# Cheat_Code.net
KiCad netlist of a schematic drawn in EAGLE
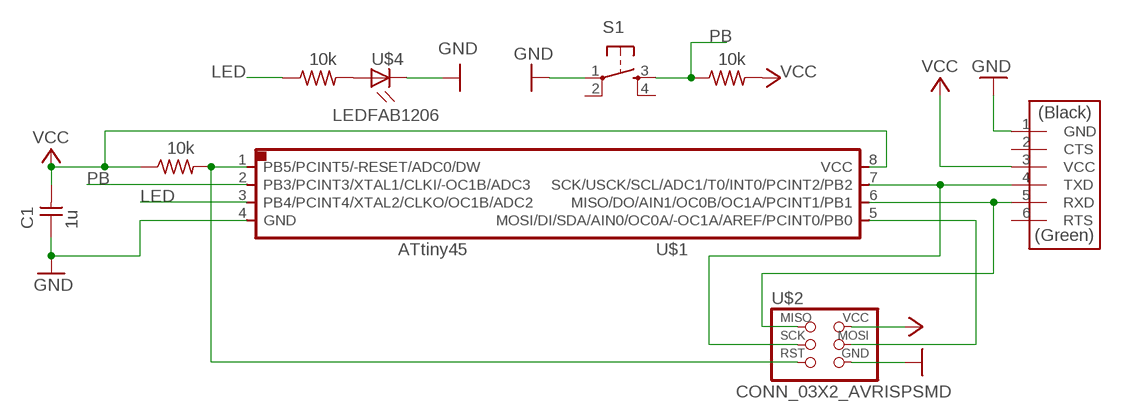
[diagram p0: schematic, sheet 1]

(export (version "E")
  (design (tool "Eeschema 10.0.6"))
  (components
    (comp (ref "C1")
      (value "1u")
      (footprint "eagle-import:C1206FAB")
      (libsource (lib "eagle-import") (part "CAP_UNPOLARIZEDFAB"))
    )
    (comp (ref "R1")
      (value "10k")
      (footprint "eagle-import:R1206")
      (libsource (lib "eagle-import") (part "R1206"))
    )
    (comp (ref "R2")
      (value "10k")
      (footprint "eagle-import:R1206")
      (libsource (lib "eagle-import") (part "R1206"))
    )
    (comp (ref "R3")
      (value "10k")
      (footprint "eagle-import:R1206")
      (libsource (lib "eagle-import") (part "R1206"))
    )
    (comp (ref "S1")
      (value "SW_SWITCH_TACTILE_6MM6MM_SWITCH")
      (footprint "eagle-import:6MM_SWITCH")
      (libsource (lib "eagle-import") (part "SW_SWITCH_TACTILE_6MM6MM_SWITCH"))
    )
    (comp (ref "U$1")
      (value "UC_ATTINY45SI")
      (footprint "eagle-import:SOIC8")
      (libsource (lib "eagle-import") (part "UC_ATTINY45SI"))
    )
    (comp (ref "U$2")
      (value "CONN_03X2_AVRISPSMD")
      (footprint "eagle-import:2X03SMD")
      (libsource (lib "eagle-import") (part "CONN_03X2_AVRISPSMD"))
    )
    (comp (ref "U$3")
      (value "CONN_06_FTDI-SMD-HEADER")
      (footprint "eagle-import:1X06SMD")
      (libsource (lib "eagle-import") (part "CONN_06_FTDI-SMD-HEADER"))
    )
    (comp (ref "U$4")
      (value "LEDFAB1206")
      (footprint "eagle-import:LED1206FAB")
      (libsource (lib "eagle-import") (part "LEDFAB1206"))
    )
  )
  (nets
    (net (code "1") (name "/LED") (class "Default")
      (node (ref "R3") (pin "1") (pinfunction "1_1") (pintype "passive"))
      (node (ref "U$1") (pin "3") (pinfunction "PB4/PCINT4/XTAL2/CLKO/OC1B/ADC2_3") (pintype "bidirectional"))
    )
    (net (code "2") (name "/PB") (class "Default")
      (node (ref "R1") (pin "1") (pinfunction "1_1") (pintype "passive"))
      (node (ref "S1") (pin "3") (pinfunction "S_3") (pintype "passive"))
      (node (ref "U$1") (pin "2") (pinfunction "PB3/PCINT3/XTAL1/CLKI/-OC1B/ADC3_2") (pintype "bidirectional"))
    )
    (net (code "3") (name "GND") (class "Default")
      (node (ref "C1") (pin "1") (pinfunction "1_1") (pintype "passive"))
      (node (ref "S1") (pin "1") (pinfunction "P_1") (pintype "passive"))
      (node (ref "U$1") (pin "4") (pinfunction "GND_4") (pintype "bidirectional"))
      (node (ref "U$2") (pin "6") (pinfunction "GND_6") (pintype "passive"))
      (node (ref "U$3") (pin "1") (pinfunction "GND_1") (pintype "bidirectional"))
      (node (ref "U$4") (pin "2") (pinfunction "C_2") (pintype "passive"))
    )
    (net (code "4") (name "Net-(U$1-MISO{slash}DO{slash}AIN1{slash}OC0B{slash}OC1A{slash}PCINT1{slash}PB1)") (class "Default")
      (node (ref "U$1") (pin "6") (pinfunction "MISO/DO/AIN1/OC0B/OC1A/PCINT1/PB1_6") (pintype "bidirectional"))
      (node (ref "U$2") (pin "1") (pinfunction "MISO_1") (pintype "passive"))
      (node (ref "U$3") (pin "5") (pinfunction "RXD_5") (pintype "bidirectional"))
    )
    (net (code "5") (name "Net-(U$1-MOSI{slash}DI{slash}SDA{slash}AIN0{slash}OC0A{slash}-OC1A{slash}AREF{slash}PCINT0{slash}PB0)") (class "Default")
      (node (ref "U$1") (pin "5") (pinfunction "MOSI/DI/SDA/AIN0/OC0A/-OC1A/AREF/PCINT0/PB0_5") (pintype "bidirectional"))
      (node (ref "U$2") (pin "4") (pinfunction "MOSI_4") (pintype "passive"))
    )
    (net (code "6") (name "Net-(U$1-PB5{slash}PCINT5{slash}-RESET{slash}ADC0{slash}DW)") (class "Default")
      (node (ref "R2") (pin "2") (pinfunction "2_2") (pintype "passive"))
      (node (ref "U$1") (pin "1") (pinfunction "PB5/PCINT5/-RESET/ADC0/DW_1") (pintype "bidirectional"))
      (node (ref "U$2") (pin "5") (pinfunction "RST_5") (pintype "passive"))
    )
    (net (code "7") (name "Net-(U$1-SCK{slash}USCK{slash}SCL{slash}ADC1{slash}T0{slash}INT0{slash}PCINT2{slash}PB2)") (class "Default")
      (node (ref "U$1") (pin "7") (pinfunction "SCK/USCK/SCL/ADC1/T0/INT0/PCINT2/PB2_7") (pintype "bidirectional"))
      (node (ref "U$2") (pin "3") (pinfunction "SCK_3") (pintype "passive"))
      (node (ref "U$3") (pin "4") (pinfunction "TXD_4") (pintype "bidirectional"))
    )
    (net (code "8") (name "Net-(U$4-A)") (class "Default")
      (node (ref "R3") (pin "2") (pinfunction "2_2") (pintype "passive"))
      (node (ref "U$4") (pin "1") (pinfunction "A_1") (pintype "passive"))
    )
    (net (code "9") (name "VCC") (class "Default")
      (node (ref "C1") (pin "2") (pinfunction "2_2") (pintype "passive"))
      (node (ref "R1") (pin "2") (pinfunction "2_2") (pintype "passive"))
      (node (ref "R2") (pin "1") (pinfunction "1_1") (pintype "passive"))
      (node (ref "U$1") (pin "8") (pinfunction "VCC_8") (pintype "bidirectional"))
      (node (ref "U$2") (pin "2") (pinfunction "VCC_2") (pintype "passive"))
      (node (ref "U$3") (pin "3") (pinfunction "VCC_3") (pintype "bidirectional"))
    )
    (net (code "10") (name "unconnected-(S1-P1-Pad2)") (class "Default")
      (node (ref "S1") (pin "2") (pinfunction "P1_2") (pintype "passive"))
    )
    (net (code "11") (name "unconnected-(S1-S1-Pad4)") (class "Default")
      (node (ref "S1") (pin "4") (pinfunction "S1_4") (pintype "passive"))
    )
    (net (code "12") (name "unconnected-(U$3-CTS-Pad2)") (class "Default")
      (node (ref "U$3") (pin "2") (pinfunction "CTS_2") (pintype "bidirectional"))
    )
    (net (code "13") (name "unconnected-(U$3-RTS-Pad6)") (class "Default")
      (node (ref "U$3") (pin "6") (pinfunction "RTS_6") (pintype "bidirectional"))
    )
  )
)
